# sheet1.net
KiCad netlist of a schematic drawn in Altium Designer
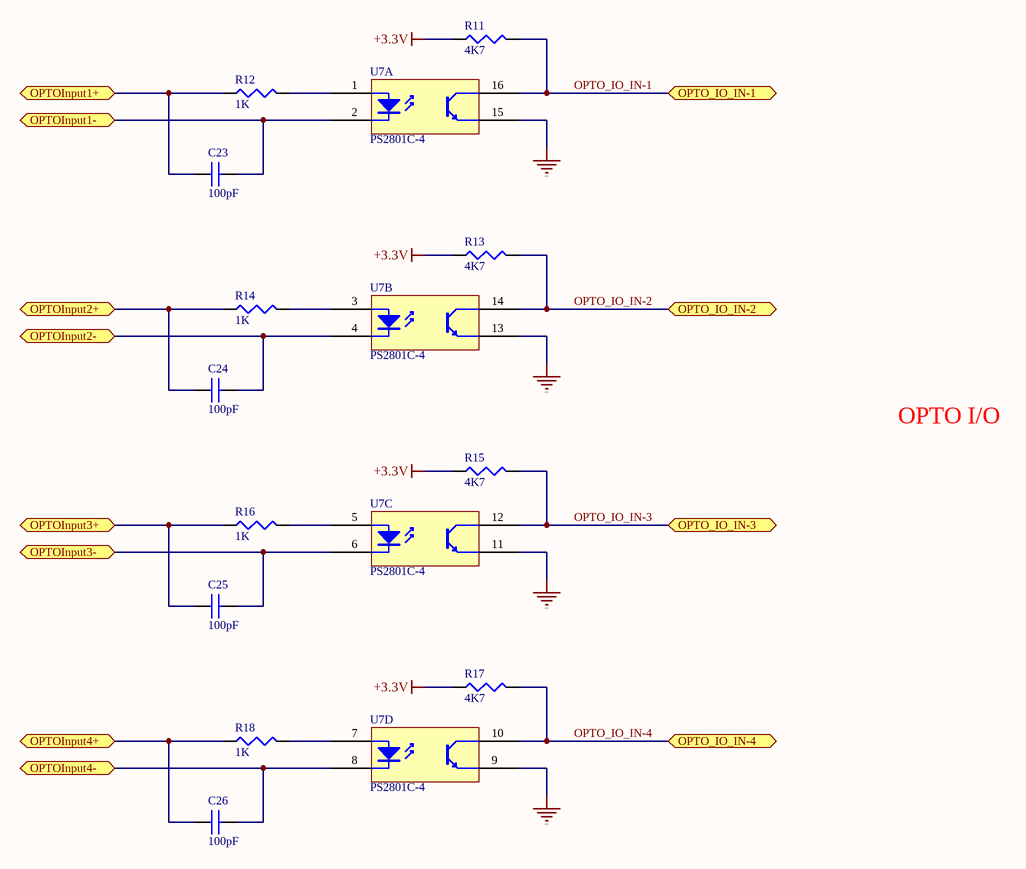
[diagram p0: sheet1.schdoc]

(export (version "E")
  (design (tool "Eeschema 10.0.6"))
  (components
    (comp (ref "C23")
      (value "100pF")
      (footprint "0805 SMD Ceramic Capacitor")
      (fields
        (field (name "VOLTAGE") "250V")
        (field (name "MANUFACTURER") "MURATA Electronics")
        (field (name "TOLERANCE") "±5%")
      )
      (libsource (lib "Capacitors") (part "C0805C101"))
    )
    (comp (ref "C24")
      (value "100pF")
      (footprint "0805 SMD Ceramic Capacitor")
      (fields
        (field (name "VOLTAGE") "250V")
        (field (name "MANUFACTURER") "MURATA Electronics")
        (field (name "TOLERANCE") "±5%")
      )
      (libsource (lib "Capacitors") (part "C0805C101"))
    )
    (comp (ref "C25")
      (value "100pF")
      (footprint "0805 SMD Ceramic Capacitor")
      (fields
        (field (name "VOLTAGE") "250V")
        (field (name "MANUFACTURER") "MURATA Electronics")
        (field (name "TOLERANCE") "±5%")
      )
      (libsource (lib "Capacitors") (part "C0805C101"))
    )
    (comp (ref "C26")
      (value "100pF")
      (footprint "0805 SMD Ceramic Capacitor")
      (fields
        (field (name "VOLTAGE") "250V")
        (field (name "MANUFACTURER") "MURATA Electronics")
        (field (name "TOLERANCE") "±5%")
      )
      (libsource (lib "Capacitors") (part "C0805C101"))
    )
    (comp (ref "R11")
      (value "4K7")
      (footprint "0805 Resistor")
      (fields
        (field (name "TOLERANCE") "±0.1%")
        (field (name "MANUFACTURER") "WELWYN")
        (field (name "Comment") "0805_4K7%1")
      )
      (libsource (lib "Resistors") (part "0805_4K7%1"))
    )
    (comp (ref "R12")
      (value "1K")
      (footprint "0805 Resistor")
      (fields
        (field (name "TOLERANCE") "±1%")
        (field (name "MANUFACTURER") "MULTICOMP")
        (field (name "Comment") "0805_1K")
      )
      (libsource (lib "Resistors") (part "0805_1K"))
    )
    (comp (ref "R13")
      (value "4K7")
      (footprint "0805 Resistor")
      (fields
        (field (name "TOLERANCE") "±0.1%")
        (field (name "MANUFACTURER") "WELWYN")
        (field (name "Comment") "0805_4K7%1")
      )
      (libsource (lib "Resistors") (part "0805_4K7%1"))
    )
    (comp (ref "R14")
      (value "1K")
      (footprint "0805 Resistor")
      (fields
        (field (name "TOLERANCE") "±1%")
        (field (name "MANUFACTURER") "MULTICOMP")
        (field (name "Comment") "0805_1K")
      )
      (libsource (lib "Resistors") (part "0805_1K"))
    )
    (comp (ref "R15")
      (value "4K7")
      (footprint "0805 Resistor")
      (fields
        (field (name "TOLERANCE") "±0.1%")
        (field (name "MANUFACTURER") "WELWYN")
        (field (name "Comment") "0805_4K7%1")
      )
      (libsource (lib "Resistors") (part "0805_4K7%1"))
    )
    (comp (ref "R16")
      (value "1K")
      (footprint "0805 Resistor")
      (fields
        (field (name "TOLERANCE") "±1%")
        (field (name "MANUFACTURER") "MULTICOMP")
        (field (name "Comment") "0805_1K")
      )
      (libsource (lib "Resistors") (part "0805_1K"))
    )
    (comp (ref "R17")
      (value "4K7")
      (footprint "0805 Resistor")
      (fields
        (field (name "TOLERANCE") "±0.1%")
        (field (name "MANUFACTURER") "WELWYN")
        (field (name "Comment") "0805_4K7%1")
      )
      (libsource (lib "Resistors") (part "0805_4K7%1"))
    )
    (comp (ref "R18")
      (value "1K")
      (footprint "0805 Resistor")
      (fields
        (field (name "TOLERANCE") "±1%")
        (field (name "MANUFACTURER") "MULTICOMP")
        (field (name "Comment") "0805_1K")
      )
      (libsource (lib "Resistors") (part "0805_1K"))
    )
    (comp (ref "U7")
      (value "PS2801C-4")
      (footprint "SO16")
      (fields (field (name "MANUFACTURER") "NEC") (field (name "Comment") "PS2801C-4_Discrete"))
      (libsource (lib "PS2801C-4") (part "PS2801C-4_Discrete"))
    )
  )
  (nets
    (net (code "1") (name "+3.3V") (class "Default")
      (node (ref "R11") (pin "1") (pinfunction "1_1") (pintype "passive"))
      (node (ref "R13") (pin "1") (pinfunction "1_1") (pintype "passive"))
      (node (ref "R15") (pin "1") (pinfunction "1_1") (pintype "passive"))
      (node (ref "R17") (pin "1") (pinfunction "1_1") (pintype "passive"))
    )
    (net (code "2") (name "/OPTOInput1+") (class "Default")
      (node (ref "C23") (pin "1") (pinfunction "1_1") (pintype "passive"))
      (node (ref "R12") (pin "1") (pinfunction "1_1") (pintype "passive"))
    )
    (net (code "3") (name "/OPTOInput1-") (class "Default")
      (node (ref "C23") (pin "2") (pinfunction "2_2") (pintype "passive"))
      (node (ref "U7") (pin "2") (pintype "passive"))
    )
    (net (code "4") (name "/OPTOInput2+") (class "Default")
      (node (ref "C24") (pin "1") (pinfunction "1_1") (pintype "passive"))
      (node (ref "R14") (pin "1") (pinfunction "1_1") (pintype "passive"))
    )
    (net (code "5") (name "/OPTOInput2-") (class "Default")
      (node (ref "C24") (pin "2") (pinfunction "2_2") (pintype "passive"))
      (node (ref "U7") (pin "4") (pintype "passive"))
    )
    (net (code "6") (name "/OPTOInput3+") (class "Default")
      (node (ref "C25") (pin "1") (pinfunction "1_1") (pintype "passive"))
      (node (ref "R16") (pin "1") (pinfunction "1_1") (pintype "passive"))
    )
    (net (code "7") (name "/OPTOInput3-") (class "Default")
      (node (ref "C25") (pin "2") (pinfunction "2_2") (pintype "passive"))
      (node (ref "U7") (pin "6") (pintype "passive"))
    )
    (net (code "8") (name "/OPTOInput4+") (class "Default")
      (node (ref "C26") (pin "1") (pinfunction "1_1") (pintype "passive"))
      (node (ref "R18") (pin "1") (pinfunction "1_1") (pintype "passive"))
    )
    (net (code "9") (name "/OPTOInput4-") (class "Default")
      (node (ref "C26") (pin "2") (pinfunction "2_2") (pintype "passive"))
      (node (ref "U7") (pin "8") (pintype "passive"))
    )
    (net (code "10") (name "/OPTO_IO_IN-1") (class "Default")
      (node (ref "R11") (pin "2") (pinfunction "2_2") (pintype "passive"))
      (node (ref "U7") (pin "16") (pintype "passive"))
    )
    (net (code "11") (name "/OPTO_IO_IN-2") (class "Default")
      (node (ref "R13") (pin "2") (pinfunction "2_2") (pintype "passive"))
      (node (ref "U7") (pin "14") (pintype "passive"))
    )
    (net (code "12") (name "/OPTO_IO_IN-3") (class "Default")
      (node (ref "R15") (pin "2") (pinfunction "2_2") (pintype "passive"))
      (node (ref "U7") (pin "12") (pintype "passive"))
    )
    (net (code "13") (name "/OPTO_IO_IN-4") (class "Default")
      (node (ref "R17") (pin "2") (pinfunction "2_2") (pintype "passive"))
      (node (ref "U7") (pin "10") (pintype "passive"))
    )
    (net (code "14") (name "GND") (class "Default")
      (node (ref "U7") (pin "11") (pintype "passive"))
      (node (ref "U7") (pin "13") (pintype "passive"))
      (node (ref "U7") (pin "15") (pintype "passive"))
      (node (ref "U7") (pin "9") (pintype "passive"))
    )
    (net (code "15") (name "Net-(R12-Pad2)") (class "Default")
      (node (ref "R12") (pin "2") (pinfunction "2_2") (pintype "passive"))
      (node (ref "U7") (pin "1") (pintype "passive"))
    )
    (net (code "16") (name "Net-(R14-Pad2)") (class "Default")
      (node (ref "R14") (pin "2") (pinfunction "2_2") (pintype "passive"))
      (node (ref "U7") (pin "3") (pintype "passive"))
    )
    (net (code "17") (name "Net-(R16-Pad2)") (class "Default")
      (node (ref "R16") (pin "2") (pinfunction "2_2") (pintype "passive"))
      (node (ref "U7") (pin "5") (pintype "passive"))
    )
    (net (code "18") (name "Net-(R18-Pad2)") (class "Default")
      (node (ref "R18") (pin "2") (pinfunction "2_2") (pintype "passive"))
      (node (ref "U7") (pin "7") (pintype "passive"))
    )
  )
)
